# Sheet1.net
KiCad netlist of a schematic drawn in Altium Designer
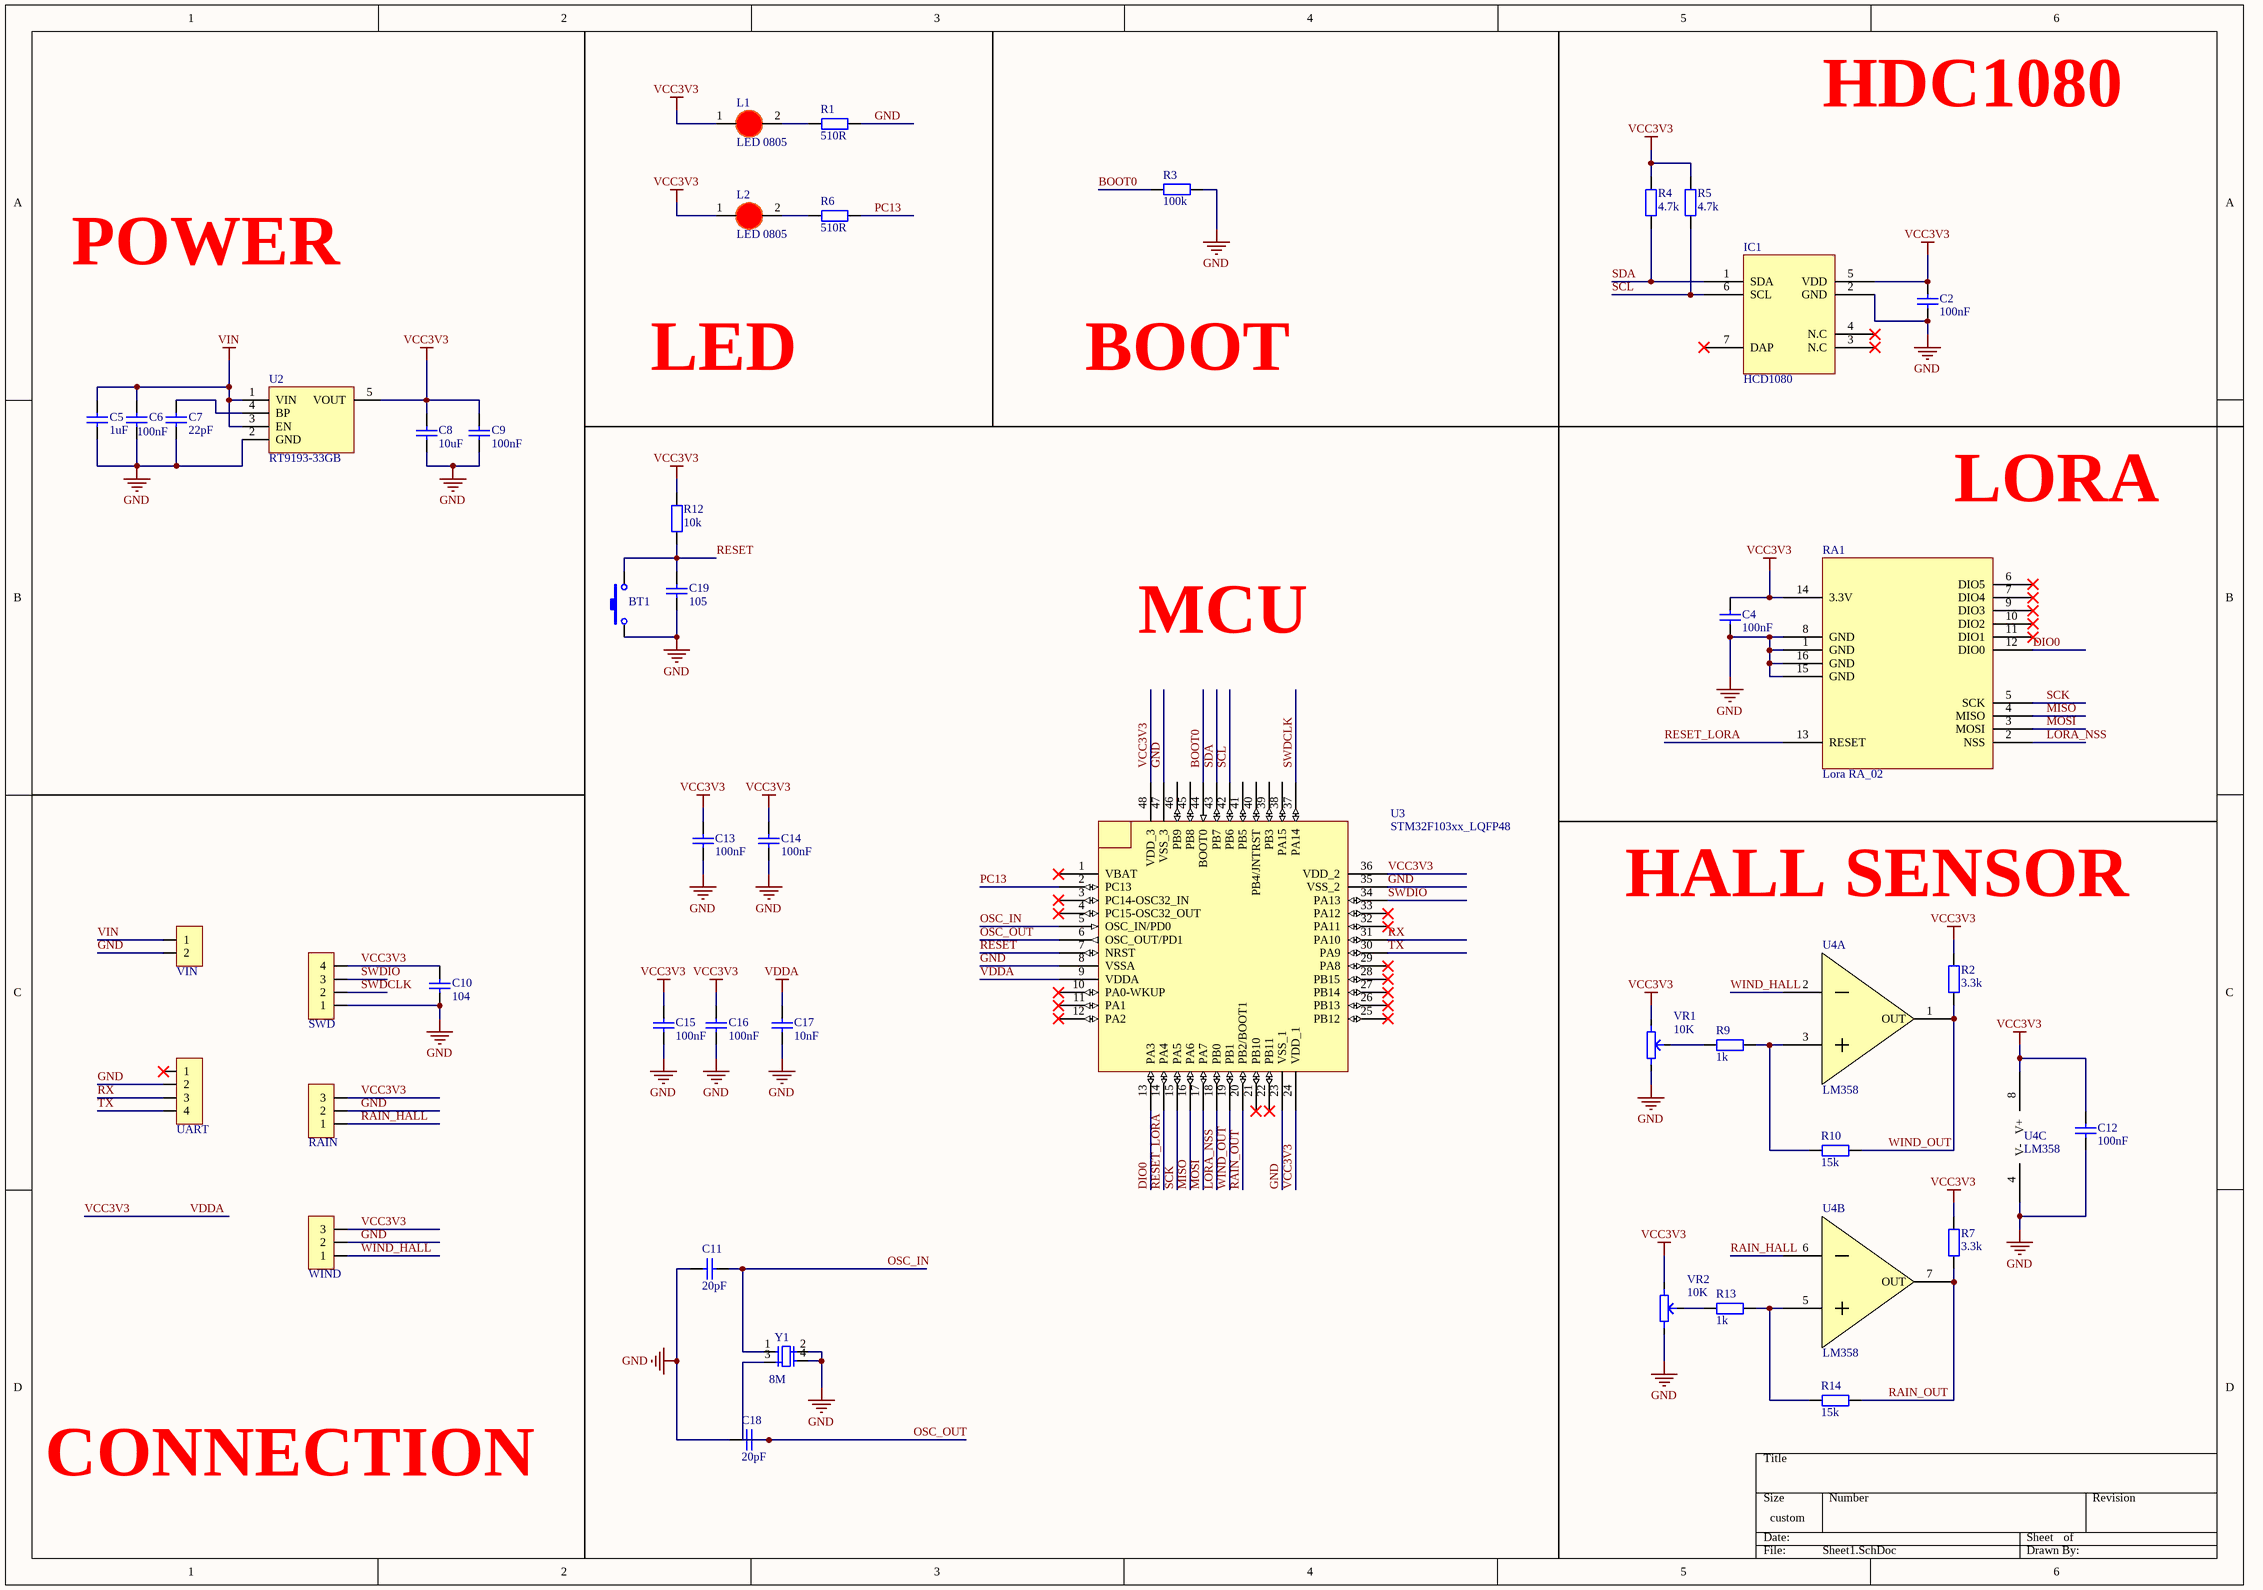
[diagram p0: Sheet1.SchDoc]

(export (version "E")
  (design (tool "Eeschema 10.0.6"))
  (components
    (comp (ref "BT1")
      (value "Nut Nhan 2 Chan SMD 3x6x2.5")
      (footprint "Nut Nhan 2 Chan SMD 3x6x2.5")
      (libsource (lib "Altium_Lib_by_KhueNguyenCreator") (part "Nut Nhan 2 Chan SMD 3x6x2.5"))
    )
    (comp (ref "C2")
      (value "100nF")
      (footprint "tu 0603")
      (description "Dán")
      (libsource (lib "Altium_Lib_by_KhueNguyenCreator") (part "Tu 0603 104 50V 10%"))
    )
    (comp (ref "C4")
      (value "100nF")
      (footprint "tu 0603")
      (description "Dán")
      (libsource (lib "Altium_Lib_by_KhueNguyenCreator") (part "Tu 0603 104 50V 10%"))
    )
    (comp (ref "C5")
      (value "1uF")
      (footprint "tu 0603")
      (description "Dán")
      (libsource (lib "Altium_Lib_by_KhueNguyenCreator") (part "Tu 0603 105 16V 20%"))
    )
    (comp (ref "C6")
      (value "100nF")
      (footprint "tu 0603")
      (description "Dán")
      (libsource (lib "Altium_Lib_by_KhueNguyenCreator") (part "Tu 0603 104 50V 10%"))
    )
    (comp (ref "C7")
      (value "22pF")
      (footprint "tu 0603")
      (description "Dán")
      (libsource (lib "Altium_Lib_by_KhueNguyenCreator") (part "Tu 0603 22pF 50V 10%"))
    )
    (comp (ref "C8")
      (value "10uF")
      (footprint "tu 0603")
      (description "Dán")
      (libsource (lib "Altium_Lib_by_KhueNguyenCreator") (part "Tu 0603 106 16V 20%"))
    )
    (comp (ref "C9")
      (value "100nF")
      (footprint "tu 0603")
      (description "Dán")
      (libsource (lib "Altium_Lib_by_KhueNguyenCreator") (part "Tu 0603 104 50V 10%"))
    )
    (comp (ref "C10")
      (value "104")
      (footprint "tu 0603")
      (description "Dán")
      (libsource (lib "Altium_Lib_by_KhueNguyenCreator") (part "Tu 0603 104 50V 10%"))
    )
    (comp (ref "C11")
      (value "20pF")
      (footprint "tu 0603")
      (description "Dán")
      (libsource (lib "Altium_Lib_by_KhueNguyenCreator") (part "Tu 0805 20pF 50V 10%"))
    )
    (comp (ref "C12")
      (value "100nF")
      (footprint "tu 0603")
      (description "Dán")
      (libsource (lib "Altium_Lib_by_KhueNguyenCreator") (part "Tu 0805 104 50V 10%"))
    )
    (comp (ref "C13")
      (value "100nF")
      (footprint "tu 0603")
      (description "Dán")
      (libsource (lib "Altium_Lib_by_KhueNguyenCreator") (part "Tu 0603 104 50V 10%"))
    )
    (comp (ref "C14")
      (value "100nF")
      (footprint "tu 0603")
      (description "Dán")
      (libsource (lib "Altium_Lib_by_KhueNguyenCreator") (part "Tu 0603 104 50V 10%"))
    )
    (comp (ref "C15")
      (value "100nF")
      (footprint "tu 0603")
      (description "Dán")
      (libsource (lib "Altium_Lib_by_KhueNguyenCreator") (part "Tu 0603 104 50V 10%"))
    )
    (comp (ref "C16")
      (value "100nF")
      (footprint "tu 0603")
      (description "Dán")
      (libsource (lib "Altium_Lib_by_KhueNguyenCreator") (part "Tu 0603 104 50V 10%"))
    )
    (comp (ref "C17")
      (value "10nF")
      (footprint "tu 0603")
      (description "Dán")
      (libsource (lib "Altium_Lib_by_KhueNguyenCreator") (part "Tu 0603 103 50V 10%"))
    )
    (comp (ref "C18")
      (value "20pF")
      (footprint "tu 0603")
      (description "Dán")
      (libsource (lib "Altium_Lib_by_KhueNguyenCreator") (part "Tu 0805 20pF 50V 10%"))
    )
    (comp (ref "C19")
      (value "105")
      (footprint "tu 0603")
      (description "Dán")
      (libsource (lib "Altium_Lib_by_KhueNguyenCreator") (part "Tu 0603 105 50V 10%"))
    )
    (comp (ref "IC1") (value "HCD1080") (footprint "HDC1080") (libsource (lib "Schlib1") (part "HCD1080")))
    (comp (ref "JP1")
      (value "VIN")
      (footprint "JP 1x2 DT")
      (description "Cắm")
      (libsource (lib "Altium_Lib_by_KhueNguyenCreator") (part "JP 1x2 2.54 Duc Thang"))
    )
    (comp (ref "JP2")
      (value "SWD")
      (footprint "JP 1x4 DT")
      (description "Cắm")
      (libsource (lib "") (part "JP 1x4 2.54 Duc Thang_1"))
    )
    (comp (ref "JP3")
      (value "UART")
      (footprint "JP 1x4 DT")
      (description "Cắm")
      (libsource (lib "Altium_Lib_by_KhueNguyenCreator") (part "JP 1x4 2.54 Duc Thang"))
    )
    (comp (ref "JP4")
      (value "RAIN")
      (footprint "JP 1x3 CT")
      (description "Cắm")
      (libsource (lib "Altium_Lib_by_KhueNguyenCreator") (part "JP 1x3 2.54 Cai Thang"))
    )
    (comp (ref "JP5")
      (value "WIND")
      (footprint "JP 1x3 CT")
      (description "Cắm")
      (libsource (lib "Altium_Lib_by_KhueNguyenCreator") (part "JP 1x3 2.54 Cai Thang"))
    )
    (comp (ref "L1")
      (value "LED 0805")
      (footprint "LED-0805-Red")
      (description "Dán")
      (libsource (lib "Altium_Lib_by_KhueNguyenCreator") (part "LED 0805 Do"))
    )
    (comp (ref "L2")
      (value "LED 0805")
      (footprint "LED-0805-Red")
      (description "Dán")
      (libsource (lib "Altium_Lib_by_KhueNguyenCreator") (part "LED 0805 Do"))
    )
    (comp (ref "R1")
      (value "510R")
      (footprint "tro smd 0603")
      (description "Dán")
      (libsource (lib "Altium_Lib_by_KhueNguyenCreator") (part "Tro 0603 5% 510R"))
    )
    (comp (ref "R2")
      (value "3.3k")
      (footprint "tro smd 0603")
      (description "Dán")
      (libsource (lib "Altium_Lib_by_KhueNguyenCreator") (part "Tro 0603 5% 3.3k"))
    )
    (comp (ref "R3")
      (value "100k")
      (footprint "tro smd 0603")
      (description "Dán")
      (libsource (lib "Altium_Lib_by_KhueNguyenCreator") (part "Tro 0603 5% 100k"))
    )
    (comp (ref "R4")
      (value "4.7k")
      (footprint "tro smd 0603")
      (description "Dán")
      (libsource (lib "Altium_Lib_by_KhueNguyenCreator") (part "Tro 0603 1% 1k"))
    )
    (comp (ref "R5")
      (value "4.7k")
      (footprint "tro smd 0603")
      (description "Dán")
      (libsource (lib "Altium_Lib_by_KhueNguyenCreator") (part "Tro 0603 1% 1k"))
    )
    (comp (ref "R6")
      (value "510R")
      (footprint "tro smd 0603")
      (description "Dán")
      (libsource (lib "Altium_Lib_by_KhueNguyenCreator") (part "Tro 0603 5% 510R"))
    )
    (comp (ref "R7")
      (value "3.3k")
      (footprint "tro smd 0603")
      (description "Dán")
      (libsource (lib "Altium_Lib_by_KhueNguyenCreator") (part "Tro 0603 5% 3.3k"))
    )
    (comp (ref "R9")
      (value "1k")
      (footprint "tro smd 0603")
      (description "Dán")
      (libsource (lib "Altium_Lib_by_KhueNguyenCreator") (part "Tro 0805 5% 2.2k"))
    )
    (comp (ref "R10")
      (value "15k")
      (footprint "tro smd 0603")
      (description "Dán")
      (libsource (lib "Altium_Lib_by_KhueNguyenCreator") (part "Tro 0805 5% 6.8k"))
    )
    (comp (ref "R12")
      (value "10k")
      (footprint "tro smd 0603")
      (description "Dán")
      (libsource (lib "Altium_Lib_by_KhueNguyenCreator") (part "Tro 0603 1% 10k"))
    )
    (comp (ref "R13")
      (value "1k")
      (footprint "tro smd 0603")
      (description "Dán")
      (libsource (lib "Altium_Lib_by_KhueNguyenCreator") (part "Tro 0805 5% 2.2k"))
    )
    (comp (ref "R14")
      (value "15k")
      (footprint "tro smd 0603")
      (description "Dán")
      (libsource (lib "Altium_Lib_by_KhueNguyenCreator") (part "Tro 0805 5% 6.8k"))
    )
    (comp (ref "RA1")
      (value "Lora RA_02")
      (footprint "SOP16")
      (libsource (lib "Schlib1") (part "Lora RA_02"))
    )
    (comp (ref "U2")
      (value "RT9193-33GB")
      (footprint "SOT23-5")
      (description "Linear Voltage Regulator IC 1 Output 300mA SOT-23-5")
      (fields (field (name "MANUFACTURER") "Richtek USA Inc."))
      (libsource (lib "Altium_Lib_by_KhueNguyenCreator") (part "REG_5.5V-3.3V-0.3A-1W-SOT-23-5"))
    )
    (comp (ref "U3")
      (value "STM32F103xx_LQFP48")
      (footprint "STM32_LQPF48")
      (fields (field (name "PUBLISHER") "Altium Limited"))
      (libsource (lib "Altium_Lib_by_KhueNguyenCreator") (part "STM32F103xx_LQFP48"))
    )
    (comp (ref "U4") (value "LM358") (footprint "LM393") (libsource (lib "Schlib1") (part "LM393")))
    (comp (ref "VR1")
      (value "10K")
      (footprint "Bien Tro Tam Giac Dung")
      (description "Cắm")
      (libsource (lib "Altium_Lib_by_KhueNguyenCreator") (part "Bien tro tam giac 100K Dung"))
    )
    (comp (ref "VR2")
      (value "10K")
      (footprint "Bien Tro Tam Giac Dung")
      (description "Cắm")
      (libsource (lib "Altium_Lib_by_KhueNguyenCreator") (part "Bien tro tam giac 100K Dung"))
    )
    (comp (ref "Y1")
      (value "8M")
      (footprint "Thach Anh 4 chan 1")
      (description "Crystal For all Crystal 2pin.")
      (libsource (lib "Altium_Lib_by_KhueNguyenCreator") (part "Thach Anh 4 Chan SMD"))
    )
  )
  (nets
    (net (code "1") (name "/BOOT0") (class "Default")
      (node (ref "R3") (pin "1") (pinfunction "1_1") (pintype "passive"))
      (node (ref "U3") (pin "44") (pinfunction "BOOT0_44") (pintype "input"))
    )
    (net (code "2") (name "/DIO0") (class "Default")
      (node (ref "RA1") (pin "12") (pinfunction "DIO0_12") (pintype "passive"))
      (node (ref "U3") (pin "13") (pinfunction "PA3_13") (pintype "bidirectional"))
    )
    (net (code "3") (name "/LORA_NSS") (class "Default")
      (node (ref "RA1") (pin "2") (pinfunction "NSS_2") (pintype "passive"))
      (node (ref "U3") (pin "18") (pinfunction "PB0_18") (pintype "bidirectional"))
    )
    (net (code "4") (name "/MISO") (class "Default")
      (node (ref "RA1") (pin "4") (pinfunction "MISO_4") (pintype "passive"))
      (node (ref "U3") (pin "16") (pinfunction "PA6_16") (pintype "bidirectional"))
    )
    (net (code "5") (name "/MOSI") (class "Default")
      (node (ref "RA1") (pin "3") (pinfunction "MOSI_3") (pintype "passive"))
      (node (ref "U3") (pin "17") (pinfunction "PA7_17") (pintype "bidirectional"))
    )
    (net (code "6") (name "/OSC_IN") (class "Default")
      (node (ref "C11") (pin "1") (pinfunction "1_1") (pintype "passive"))
      (node (ref "U3") (pin "5") (pinfunction "OSC_IN/PD0_5") (pintype "input"))
      (node (ref "Y1") (pin "1") (pinfunction "1_1") (pintype "passive"))
    )
    (net (code "7") (name "/OSC_OUT") (class "Default")
      (node (ref "C18") (pin "1") (pinfunction "1_1") (pintype "passive"))
      (node (ref "U3") (pin "6") (pinfunction "OSC_OUT/PD1_6") (pintype "output"))
      (node (ref "Y1") (pin "3") (pinfunction "3_3") (pintype "passive"))
    )
    (net (code "8") (name "/PC13") (class "Default")
      (node (ref "R6") (pin "2") (pinfunction "2_2") (pintype "passive"))
      (node (ref "U3") (pin "2") (pinfunction "PC13_2") (pintype "bidirectional"))
    )
    (net (code "9") (name "/RAIN_HALL") (class "Default")
      (node (ref "JP4") (pin "1") (pinfunction "1_1") (pintype "passive"))
      (node (ref "U4") (pin "6") (pinfunction "-_6") (pintype "passive"))
    )
    (net (code "10") (name "/RAIN_OUT") (class "Default")
      (node (ref "R14") (pin "2") (pinfunction "2_2") (pintype "passive"))
      (node (ref "R7") (pin "1") (pinfunction "1_1") (pintype "passive"))
      (node (ref "U3") (pin "20") (pinfunction "PB2/BOOT1_20") (pintype "bidirectional"))
      (node (ref "U4") (pin "7") (pinfunction "OUT_7") (pintype "passive"))
    )
    (net (code "11") (name "/RESET") (class "Default")
      (node (ref "BT1") (pin "2") (pinfunction "2_2") (pintype "passive"))
      (node (ref "C19") (pin "1") (pinfunction "1_1") (pintype "passive"))
      (node (ref "R12") (pin "1") (pinfunction "1_1") (pintype "passive"))
      (node (ref "U3") (pin "7") (pinfunction "NRST_7") (pintype "bidirectional"))
    )
    (net (code "12") (name "/RESET_LORA") (class "Default")
      (node (ref "RA1") (pin "13") (pinfunction "RESET_13") (pintype "passive"))
      (node (ref "U3") (pin "14") (pinfunction "PA4_14") (pintype "bidirectional"))
    )
    (net (code "13") (name "/RX") (class "Default")
      (node (ref "JP3") (pin "3") (pinfunction "3_3") (pintype "passive"))
      (node (ref "U3") (pin "31") (pinfunction "PA10_31") (pintype "bidirectional"))
    )
    (net (code "14") (name "/SCK") (class "Default")
      (node (ref "RA1") (pin "5") (pinfunction "SCK_5") (pintype "passive"))
      (node (ref "U3") (pin "15") (pinfunction "PA5_15") (pintype "bidirectional"))
    )
    (net (code "15") (name "/SCL") (class "Default")
      (node (ref "IC1") (pin "6") (pinfunction "SCL_6") (pintype "passive"))
      (node (ref "R5") (pin "1") (pinfunction "1_1") (pintype "passive"))
      (node (ref "U3") (pin "42") (pinfunction "PB6_42") (pintype "bidirectional"))
    )
    (net (code "16") (name "/SDA") (class "Default")
      (node (ref "IC1") (pin "1") (pinfunction "SDA_1") (pintype "passive"))
      (node (ref "R4") (pin "1") (pinfunction "1_1") (pintype "passive"))
      (node (ref "U3") (pin "43") (pinfunction "PB7_43") (pintype "bidirectional"))
    )
    (net (code "17") (name "/SWDCLK") (class "Default")
      (node (ref "JP2") (pin "2") (pinfunction "2_2") (pintype "passive"))
      (node (ref "U3") (pin "37") (pinfunction "PA14_37") (pintype "bidirectional"))
    )
    (net (code "18") (name "/SWDIO") (class "Default")
      (node (ref "JP2") (pin "3") (pinfunction "3_3") (pintype "passive"))
      (node (ref "U3") (pin "34") (pinfunction "PA13_34") (pintype "bidirectional"))
    )
    (net (code "19") (name "/TX") (class "Default")
      (node (ref "JP3") (pin "4") (pinfunction "4_4") (pintype "passive"))
      (node (ref "U3") (pin "30") (pinfunction "PA9_30") (pintype "bidirectional"))
    )
    (net (code "20") (name "/WIND_HALL") (class "Default")
      (node (ref "JP5") (pin "1") (pinfunction "1_1") (pintype "passive"))
      (node (ref "U4") (pin "2") (pinfunction "-_2") (pintype "passive"))
    )
    (net (code "21") (name "/WIND_OUT") (class "Default")
      (node (ref "R10") (pin "2") (pinfunction "2_2") (pintype "passive"))
      (node (ref "R2") (pin "1") (pinfunction "1_1") (pintype "passive"))
      (node (ref "U3") (pin "19") (pinfunction "PB1_19") (pintype "bidirectional"))
      (node (ref "U4") (pin "1") (pinfunction "OUT_1") (pintype "passive"))
    )
    (net (code "22") (name "GND") (class "Default")
      (node (ref "BT1") (pin "1") (pinfunction "1_1") (pintype "passive"))
      (node (ref "C10") (pin "2") (pinfunction "2_2") (pintype "passive"))
      (node (ref "C11") (pin "2") (pinfunction "2_2") (pintype "passive"))
      (node (ref "C12") (pin "2") (pinfunction "2_2") (pintype "passive"))
      (node (ref "C13") (pin "2") (pinfunction "2_2") (pintype "passive"))
      (node (ref "C14") (pin "2") (pinfunction "2_2") (pintype "passive"))
      (node (ref "C15") (pin "2") (pinfunction "2_2") (pintype "passive"))
      (node (ref "C16") (pin "2") (pinfunction "2_2") (pintype "passive"))
      (node (ref "C17") (pin "2") (pinfunction "2_2") (pintype "passive"))
      (node (ref "C18") (pin "2") (pinfunction "2_2") (pintype "passive"))
      (node (ref "C19") (pin "2") (pinfunction "2_2") (pintype "passive"))
      (node (ref "C2") (pin "2") (pinfunction "2_2") (pintype "passive"))
      (node (ref "C4") (pin "2") (pinfunction "2_2") (pintype "passive"))
      (node (ref "C5") (pin "2") (pinfunction "2_2") (pintype "passive"))
      (node (ref "C6") (pin "2") (pinfunction "2_2") (pintype "passive"))
      (node (ref "C7") (pin "2") (pinfunction "2_2") (pintype "passive"))
      (node (ref "C8") (pin "2") (pinfunction "2_2") (pintype "passive"))
      (node (ref "C9") (pin "2") (pinfunction "2_2") (pintype "passive"))
      (node (ref "IC1") (pin "2") (pinfunction "GND_2") (pintype "passive"))
      (node (ref "JP1") (pin "2") (pinfunction "2_2") (pintype "passive"))
      (node (ref "JP2") (pin "1") (pinfunction "1_1") (pintype "passive"))
      (node (ref "JP3") (pin "2") (pinfunction "2_2") (pintype "passive"))
      (node (ref "JP4") (pin "2") (pinfunction "2_2") (pintype "passive"))
      (node (ref "JP5") (pin "2") (pinfunction "2_2") (pintype "passive"))
      (node (ref "R1") (pin "2") (pinfunction "2_2") (pintype "passive"))
      (node (ref "R3") (pin "2") (pinfunction "2_2") (pintype "passive"))
      (node (ref "RA1") (pin "1") (pinfunction "GND_1") (pintype "passive"))
      (node (ref "RA1") (pin "15") (pinfunction "GND_15") (pintype "passive"))
      (node (ref "RA1") (pin "16") (pinfunction "GND_16") (pintype "passive"))
      (node (ref "RA1") (pin "8") (pinfunction "GND_8") (pintype "passive"))
      (node (ref "U2") (pin "2") (pinfunction "GND_2") (pintype "passive"))
      (node (ref "U3") (pin "23") (pinfunction "VSS_1_23") (pintype "power_in"))
      (node (ref "U3") (pin "35") (pinfunction "VSS_2_35") (pintype "power_in"))
      (node (ref "U3") (pin "47") (pinfunction "VSS_3_47") (pintype "power_in"))
      (node (ref "U3") (pin "8") (pinfunction "VSSA_8") (pintype "power_in"))
      (node (ref "U4") (pin "4") (pinfunction "V-_4") (pintype "passive"))
      (node (ref "VR1") (pin "3") (pinfunction "3_3") (pintype "passive"))
      (node (ref "VR2") (pin "3") (pinfunction "3_3") (pintype "passive"))
      (node (ref "Y1") (pin "2") (pinfunction "2_2") (pintype "passive"))
      (node (ref "Y1") (pin "4") (pinfunction "4_4") (pintype "passive"))
    )
    (net (code "23") (name "Net-(L1-K)") (class "Default")
      (node (ref "L1") (pin "2") (pinfunction "K_2") (pintype "passive"))
      (node (ref "R1") (pin "1") (pinfunction "1_1") (pintype "passive"))
    )
    (net (code "24") (name "Net-(L2-K)") (class "Default")
      (node (ref "L2") (pin "2") (pinfunction "K_2") (pintype "passive"))
      (node (ref "R6") (pin "1") (pinfunction "1_1") (pintype "passive"))
    )
    (net (code "25") (name "Net-(R9-Pad1)") (class "Default")
      (node (ref "R9") (pin "1") (pinfunction "1_1") (pintype "passive"))
      (node (ref "VR1") (pin "2") (pinfunction "2_2") (pintype "passive"))
    )
    (net (code "26") (name "Net-(R13-Pad1)") (class "Default")
      (node (ref "R13") (pin "1") (pinfunction "1_1") (pintype "passive"))
      (node (ref "VR2") (pin "2") (pinfunction "2_2") (pintype "passive"))
    )
    (net (code "27") (name "Net-(U2-BP)") (class "Default")
      (node (ref "C7") (pin "1") (pinfunction "1_1") (pintype "passive"))
      (node (ref "U2") (pin "4") (pinfunction "BP_4") (pintype "passive"))
    )
    (net (code "28") (name "Net-(U4A-+)") (class "Default")
      (node (ref "R10") (pin "1") (pinfunction "1_1") (pintype "passive"))
      (node (ref "R9") (pin "2") (pinfunction "2_2") (pintype "passive"))
      (node (ref "U4") (pin "3") (pinfunction "+_3") (pintype "passive"))
    )
    (net (code "29") (name "Net-(U4B-+)") (class "Default")
      (node (ref "R13") (pin "2") (pinfunction "2_2") (pintype "passive"))
      (node (ref "R14") (pin "1") (pinfunction "1_1") (pintype "passive"))
      (node (ref "U4") (pin "5") (pinfunction "+_5") (pintype "passive"))
    )
    (net (code "30") (name "VCC3V3") (class "Default")
      (node (ref "C10") (pin "1") (pinfunction "1_1") (pintype "passive"))
      (node (ref "C12") (pin "1") (pinfunction "1_1") (pintype "passive"))
      (node (ref "C13") (pin "1") (pinfunction "1_1") (pintype "passive"))
      (node (ref "C14") (pin "1") (pinfunction "1_1") (pintype "passive"))
      (node (ref "C15") (pin "1") (pinfunction "1_1") (pintype "passive"))
      (node (ref "C16") (pin "1") (pinfunction "1_1") (pintype "passive"))
      (node (ref "C17") (pin "1") (pinfunction "1_1") (pintype "passive"))
      (node (ref "C2") (pin "1") (pinfunction "1_1") (pintype "passive"))
      (node (ref "C4") (pin "1") (pinfunction "1_1") (pintype "passive"))
      (node (ref "C8") (pin "1") (pinfunction "1_1") (pintype "passive"))
      (node (ref "C9") (pin "1") (pinfunction "1_1") (pintype "passive"))
      (node (ref "IC1") (pin "5") (pinfunction "VDD_5") (pintype "passive"))
      (node (ref "JP2") (pin "4") (pinfunction "4_4") (pintype "passive"))
      (node (ref "JP4") (pin "3") (pinfunction "3_3") (pintype "passive"))
      (node (ref "JP5") (pin "3") (pinfunction "3_3") (pintype "passive"))
      (node (ref "L1") (pin "1") (pinfunction "A_1") (pintype "passive"))
      (node (ref "L2") (pin "1") (pinfunction "A_1") (pintype "passive"))
      (node (ref "R12") (pin "2") (pinfunction "2_2") (pintype "passive"))
      (node (ref "R2") (pin "2") (pinfunction "2_2") (pintype "passive"))
      (node (ref "R4") (pin "2") (pinfunction "2_2") (pintype "passive"))
      (node (ref "R5") (pin "2") (pinfunction "2_2") (pintype "passive"))
      (node (ref "R7") (pin "2") (pinfunction "2_2") (pintype "passive"))
      (node (ref "RA1") (pin "14") (pinfunction "3.3V_14") (pintype "passive"))
      (node (ref "U2") (pin "5") (pinfunction "VOUT_5") (pintype "passive"))
      (node (ref "U3") (pin "24") (pinfunction "VDD_1_24") (pintype "power_in"))
      (node (ref "U3") (pin "36") (pinfunction "VDD_2_36") (pintype "power_in"))
      (node (ref "U3") (pin "48") (pinfunction "VDD_3_48") (pintype "power_in"))
      (node (ref "U3") (pin "9") (pinfunction "VDDA_9") (pintype "power_in"))
      (node (ref "U4") (pin "8") (pinfunction "V+_8") (pintype "passive"))
      (node (ref "VR1") (pin "1") (pinfunction "1_1") (pintype "passive"))
      (node (ref "VR2") (pin "1") (pinfunction "1_1") (pintype "passive"))
    )
    (net (code "31") (name "VIN") (class "Default")
      (node (ref "C5") (pin "1") (pinfunction "1_1") (pintype "passive"))
      (node (ref "C6") (pin "1") (pinfunction "1_1") (pintype "passive"))
      (node (ref "JP1") (pin "1") (pinfunction "1_1") (pintype "passive"))
      (node (ref "U2") (pin "1") (pinfunction "VIN_1") (pintype "passive"))
      (node (ref "U2") (pin "3") (pinfunction "EN_3") (pintype "passive"))
    )
    (net (code "32") (name "unconnected-(IC1-DAP-Pad7)") (class "Default")
      (node (ref "IC1") (pin "7") (pinfunction "DAP_7") (pintype "passive+no_connect"))
    )
    (net (code "33") (name "unconnected-(IC1-N.C-Pad3)") (class "Default")
      (node (ref "IC1") (pin "3") (pinfunction "N.C_3") (pintype "passive+no_connect"))
    )
    (net (code "34") (name "unconnected-(IC1-N.C-Pad4)") (class "Default")
      (node (ref "IC1") (pin "4") (pinfunction "N.C_4") (pintype "passive+no_connect"))
    )
    (net (code "35") (name "unconnected-(JP3-Pad1)") (class "Default")
      (node (ref "JP3") (pin "1") (pinfunction "1_1") (pintype "passive+no_connect"))
    )
    (net (code "36") (name "unconnected-(RA1-DIO1-Pad11)") (class "Default")
      (node (ref "RA1") (pin "11") (pinfunction "DIO1_11") (pintype "passive+no_connect"))
    )
    (net (code "37") (name "unconnected-(RA1-DIO2-Pad10)") (class "Default")
      (node (ref "RA1") (pin "10") (pinfunction "DIO2_10") (pintype "passive+no_connect"))
    )
    (net (code "38") (name "unconnected-(RA1-DIO3-Pad9)") (class "Default")
      (node (ref "RA1") (pin "9") (pinfunction "DIO3_9") (pintype "passive+no_connect"))
    )
    (net (code "39") (name "unconnected-(RA1-DIO4-Pad7)") (class "Default")
      (node (ref "RA1") (pin "7") (pinfunction "DIO4_7") (pintype "passive+no_connect"))
    )
    (net (code "40") (name "unconnected-(RA1-DIO5-Pad6)") (class "Default")
      (node (ref "RA1") (pin "6") (pinfunction "DIO5_6") (pintype "passive+no_connect"))
    )
    (net (code "41") (name "unconnected-(U3-PA0-WKUP-Pad10)") (class "Default")
      (node (ref "U3") (pin "10") (pinfunction "PA0-WKUP_10") (pintype "bidirectional+no_connect"))
    )
    (net (code "42") (name "unconnected-(U3-PA1-Pad11)") (class "Default")
      (node (ref "U3") (pin "11") (pinfunction "PA1_11") (pintype "bidirectional+no_connect"))
    )
    (net (code "43") (name "unconnected-(U3-PA2-Pad12)") (class "Default")
      (node (ref "U3") (pin "12") (pinfunction "PA2_12") (pintype "bidirectional+no_connect"))
    )
    (net (code "44") (name "unconnected-(U3-PA8-Pad29)") (class "Default")
      (node (ref "U3") (pin "29") (pinfunction "PA8_29") (pintype "bidirectional+no_connect"))
    )
    (net (code "45") (name "unconnected-(U3-PA11-Pad32)") (class "Default")
      (node (ref "U3") (pin "32") (pinfunction "PA11_32") (pintype "bidirectional+no_connect"))
    )
    (net (code "46") (name "unconnected-(U3-PA12-Pad33)") (class "Default")
      (node (ref "U3") (pin "33") (pinfunction "PA12_33") (pintype "bidirectional+no_connect"))
    )
    (net (code "47") (name "unconnected-(U3-PA15-Pad38)") (class "Default")
      (node (ref "U3") (pin "38") (pinfunction "PA15_38") (pintype "bidirectional"))
    )
    (net (code "48") (name "unconnected-(U3-PB3-Pad39)") (class "Default")
      (node (ref "U3") (pin "39") (pinfunction "PB3_39") (pintype "bidirectional"))
    )
    (net (code "49") (name "unconnected-(U3-PB4{slash}JNTRST-Pad40)") (class "Default")
      (node (ref "U3") (pin "40") (pinfunction "PB4/JNTRST_40") (pintype "bidirectional"))
    )
    (net (code "50") (name "unconnected-(U3-PB5-Pad41)") (class "Default")
      (node (ref "U3") (pin "41") (pinfunction "PB5_41") (pintype "bidirectional"))
    )
    (net (code "51") (name "unconnected-(U3-PB8-Pad45)") (class "Default")
      (node (ref "U3") (pin "45") (pinfunction "PB8_45") (pintype "bidirectional"))
    )
    (net (code "52") (name "unconnected-(U3-PB9-Pad46)") (class "Default")
      (node (ref "U3") (pin "46") (pinfunction "PB9_46") (pintype "bidirectional"))
    )
    (net (code "53") (name "unconnected-(U3-PB10-Pad21)") (class "Default")
      (node (ref "U3") (pin "21") (pinfunction "PB10_21") (pintype "bidirectional+no_connect"))
    )
    (net (code "54") (name "unconnected-(U3-PB11-Pad22)") (class "Default")
      (node (ref "U3") (pin "22") (pinfunction "PB11_22") (pintype "bidirectional+no_connect"))
    )
    (net (code "55") (name "unconnected-(U3-PB12-Pad25)") (class "Default")
      (node (ref "U3") (pin "25") (pinfunction "PB12_25") (pintype "bidirectional+no_connect"))
    )
    (net (code "56") (name "unconnected-(U3-PB13-Pad26)") (class "Default")
      (node (ref "U3") (pin "26") (pinfunction "PB13_26") (pintype "bidirectional+no_connect"))
    )
    (net (code "57") (name "unconnected-(U3-PB14-Pad27)") (class "Default")
      (node (ref "U3") (pin "27") (pinfunction "PB14_27") (pintype "bidirectional+no_connect"))
    )
    (net (code "58") (name "unconnected-(U3-PB15-Pad28)") (class "Default")
      (node (ref "U3") (pin "28") (pinfunction "PB15_28") (pintype "bidirectional+no_connect"))
    )
    (net (code "59") (name "unconnected-(U3-PC14-OSC32_IN-Pad3)") (class "Default")
      (node (ref "U3") (pin "3") (pinfunction "PC14-OSC32_IN_3") (pintype "bidirectional+no_connect"))
    )
    (net (code "60") (name "unconnected-(U3-PC15-OSC32_OUT-Pad4)") (class "Default")
      (node (ref "U3") (pin "4") (pinfunction "PC15-OSC32_OUT_4") (pintype "bidirectional+no_connect"))
    )
    (net (code "61") (name "unconnected-(U3-VBAT-Pad1)") (class "Default")
      (node (ref "U3") (pin "1") (pinfunction "VBAT_1") (pintype "power_in+no_connect"))
    )
  )
)
